# I2CInterface.net
KiCad netlist of a schematic drawn in Altium Designer
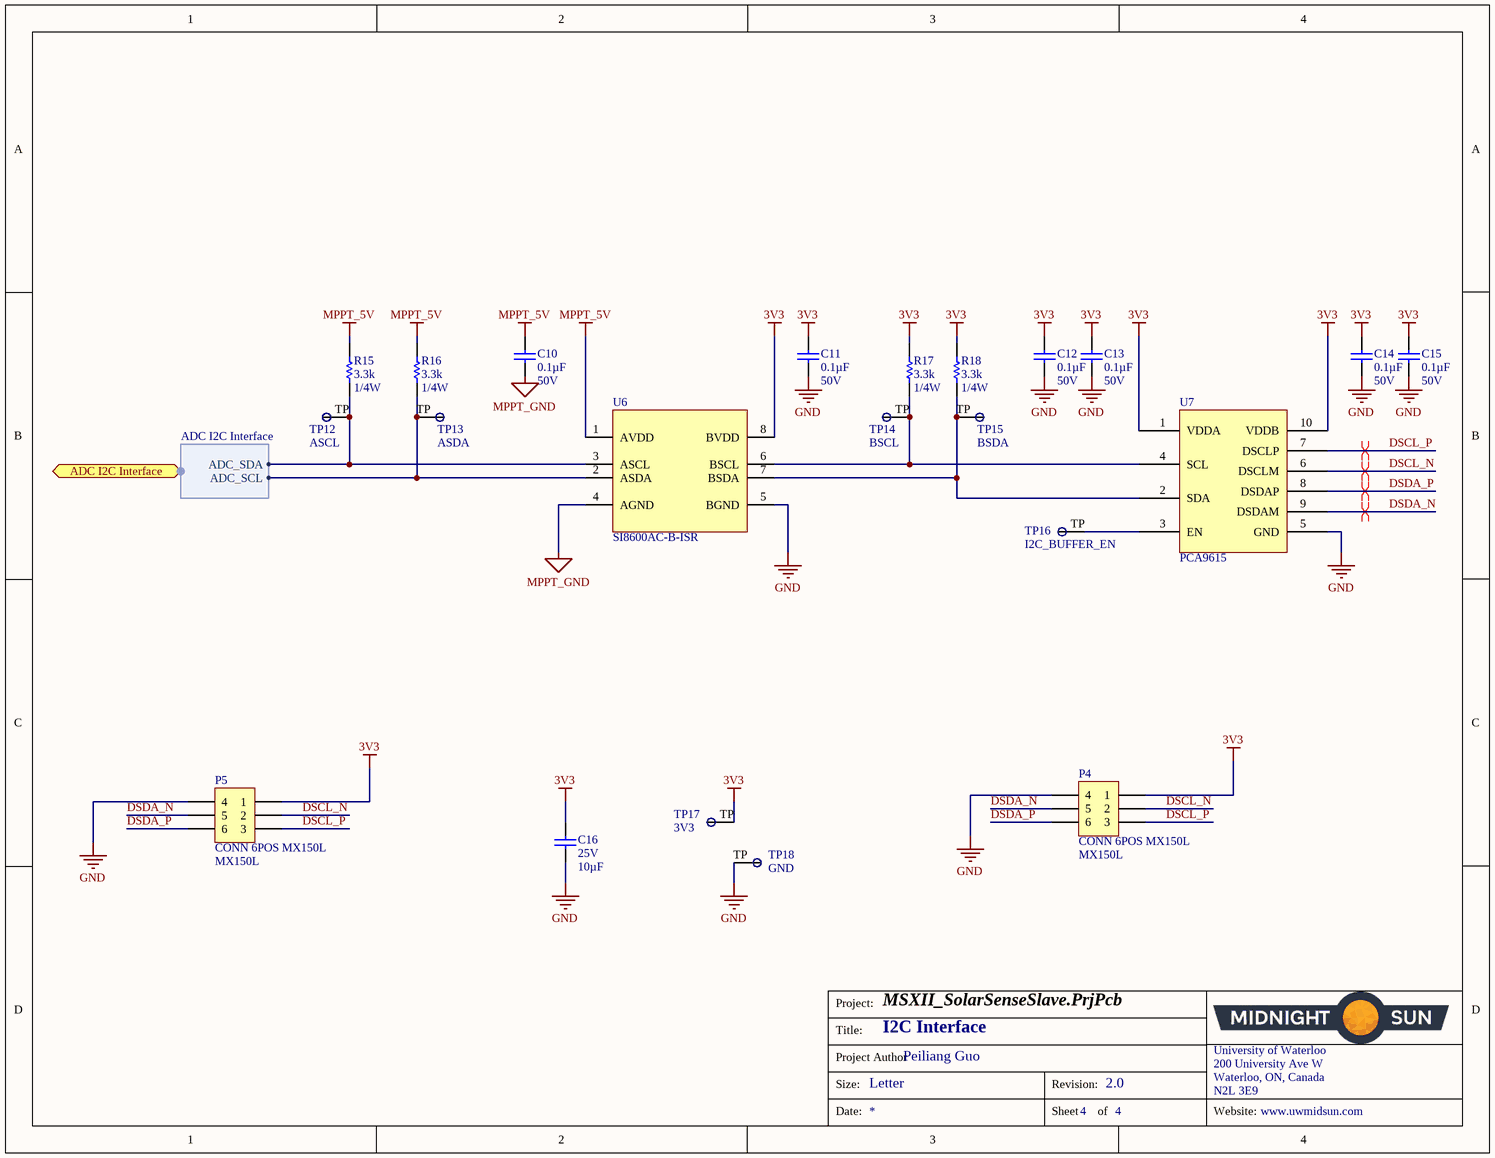
[diagram p0: I2CInterface.SchDoc]

(export (version "E")
  (design (tool "Eeschema 10.0.6"))
  (components
    (comp (ref "C10")
      (value "CAP CER 0.1UF 50V 10% X7R 0603")
      (footprint "CAP, 0603")
      (description "0.10µF ±10% 50V Ceramic Capacitor X7R 0603 (1608 Metric)")
      (fields
        (field (name "TOLERANCE") "±10%")
        (field (name "CAPACITANCE") "0.1µF")
        (field (name "VOLTAGE") "50V")
      )
      (libsource (lib "Schematic Diagrams") (part "CAP CER 0.1UF 50V 10% X7R 0603"))
    )
    (comp (ref "C11")
      (value "CAP CER 0.1UF 50V 10% X7R 0603")
      (footprint "CAP, 0603")
      (description "0.10µF ±10% 50V Ceramic Capacitor X7R 0603 (1608 Metric)")
      (fields
        (field (name "TOLERANCE") "±10%")
        (field (name "CAPACITANCE") "0.1µF")
        (field (name "VOLTAGE") "50V")
      )
      (libsource (lib "Schematic Diagrams") (part "CAP CER 0.1UF 50V 10% X7R 0603"))
    )
    (comp (ref "C12")
      (value "CAP CER 0.1UF 50V 10% X7R 0603")
      (footprint "CAP, 0603")
      (description "0.10µF ±10% 50V Ceramic Capacitor X7R 0603 (1608 Metric)")
      (fields
        (field (name "TOLERANCE") "±10%")
        (field (name "CAPACITANCE") "0.1µF")
        (field (name "VOLTAGE") "50V")
      )
      (libsource (lib "Schematic Diagrams") (part "CAP CER 0.1UF 50V 10% X7R 0603"))
    )
    (comp (ref "C13")
      (value "CAP CER 0.1UF 50V 10% X7R 0603")
      (footprint "CAP, 0603")
      (description "0.10µF ±10% 50V Ceramic Capacitor X7R 0603 (1608 Metric)")
      (fields
        (field (name "TOLERANCE") "±10%")
        (field (name "CAPACITANCE") "0.1µF")
        (field (name "VOLTAGE") "50V")
      )
      (libsource (lib "Schematic Diagrams") (part "CAP CER 0.1UF 50V 10% X7R 0603"))
    )
    (comp (ref "C14")
      (value "CAP CER 0.1UF 50V 10% X7R 0603")
      (footprint "CAP, 0603")
      (description "0.10µF ±10% 50V Ceramic Capacitor X7R 0603 (1608 Metric)")
      (fields
        (field (name "TOLERANCE") "±10%")
        (field (name "CAPACITANCE") "0.1µF")
        (field (name "VOLTAGE") "50V")
      )
      (libsource (lib "Schematic Diagrams") (part "CAP CER 0.1UF 50V 10% X7R 0603"))
    )
    (comp (ref "C15")
      (value "CAP CER 0.1UF 50V 10% X7R 0603")
      (footprint "CAP, 0603")
      (description "0.10µF ±10% 50V Ceramic Capacitor X7R 0603 (1608 Metric)")
      (fields
        (field (name "TOLERANCE") "±10%")
        (field (name "CAPACITANCE") "0.1µF")
        (field (name "VOLTAGE") "50V")
      )
      (libsource (lib "Schematic Diagrams") (part "CAP CER 0.1UF 50V 10% X7R 0603"))
    )
    (comp (ref "C16")
      (value "CAP CER 10uF 25V 10% X5R 0805")
      (footprint "CAP, 0805")
      (description "10µF ±10% 25V Ceramic Capacitor X5R 0805 (2012 Metric)")
      (fields
        (field (name "MANUFACTURER") "Murata Electronics North America")
        (field (name "MANUFACTURER PART NUMBER") "GRM21BR61E106KA73L")
        (field (name "VOLTAGE - RATED") "25V")
        (field (name "CAPACITANCE") "10µF")
      )
      (libsource (lib "Schematic Diagrams") (part "CAP CER 10uF 25V 10% X5R 0805"))
    )
    (comp (ref "P4")
      (value "CONN 6POS MX150L")
      (footprint "CONN, 6POS MX150L")
      (description "Connector Header Panel Mount, Through Hole, Right Angle 6 position 0.230\" (5.84mm)")
      (fields
        (field (name "MANUFACTURER") "Molex")
        (field (name "MANUFACTURER PART NUMBER") "19427-0018")
        (field (name "SERIES") "MX150L")
      )
      (libsource (lib "Schematic Diagrams") (part "CONN 6POS MX150L"))
    )
    (comp (ref "P5")
      (value "CONN 6POS MX150L")
      (footprint "CONN, 6POS MX150L")
      (description "Connector Header Panel Mount, Through Hole, Right Angle 6 position 0.230\" (5.84mm)")
      (fields
        (field (name "MANUFACTURER") "Molex")
        (field (name "MANUFACTURER PART NUMBER") "19427-0018")
        (field (name "SERIES") "MX150L")
      )
      (libsource (lib "Schematic Diagrams") (part "CONN 6POS MX150L"))
    )
    (comp (ref "R15")
      (value "RES 3.3K OHM 1% 1/4W 0603")
      (footprint "RES, 0603")
      (fields
        (field (name "TOLERANCE") "±1%")
        (field (name "RESISTANCE") "3.3k")
        (field (name "POWER") "1/4W")
      )
      (libsource (lib "Schematic Diagrams") (part "RES 3.3K OHM 1% 1/4W 0603"))
    )
    (comp (ref "R16")
      (value "RES 3.3K OHM 1% 1/4W 0603")
      (footprint "RES, 0603")
      (fields
        (field (name "TOLERANCE") "±1%")
        (field (name "RESISTANCE") "3.3k")
        (field (name "POWER") "1/4W")
      )
      (libsource (lib "Schematic Diagrams") (part "RES 3.3K OHM 1% 1/4W 0603"))
    )
    (comp (ref "R17")
      (value "RES 3.3K OHM 1% 1/4W 0603")
      (footprint "RES, 0603")
      (fields
        (field (name "TOLERANCE") "±1%")
        (field (name "RESISTANCE") "3.3k")
        (field (name "POWER") "1/4W")
      )
      (libsource (lib "Schematic Diagrams") (part "RES 3.3K OHM 1% 1/4W 0603"))
    )
    (comp (ref "R18")
      (value "RES 3.3K OHM 1% 1/4W 0603")
      (footprint "RES, 0603")
      (fields
        (field (name "TOLERANCE") "±1%")
        (field (name "RESISTANCE") "3.3k")
        (field (name "POWER") "1/4W")
      )
      (libsource (lib "Schematic Diagrams") (part "RES 3.3K OHM 1% 1/4W 0603"))
    )
    (comp (ref "TP12")
      (value "ASCL")
      (footprint "Test Point")
      (libsource (lib "Schematic Diagrams") (part "Test Point"))
    )
    (comp (ref "TP13")
      (value "ASDA")
      (footprint "Test Point")
      (libsource (lib "Schematic Diagrams") (part "Test Point"))
    )
    (comp (ref "TP14")
      (value "BSCL")
      (footprint "Test Point")
      (libsource (lib "Schematic Diagrams") (part "Test Point"))
    )
    (comp (ref "TP15")
      (value "BSDA")
      (footprint "Test Point")
      (libsource (lib "Schematic Diagrams") (part "Test Point"))
    )
    (comp (ref "TP16")
      (value "I2C_BUFFER_EN")
      (footprint "Test Point")
      (libsource (lib "Schematic Diagrams") (part "Test Point"))
    )
    (comp (ref "TP17")
      (value "3V3")
      (footprint "Test Point")
      (libsource (lib "Schematic Diagrams") (part "Test Point"))
    )
    (comp (ref "TP18")
      (value "GND")
      (footprint "Test Point")
      (libsource (lib "Schematic Diagrams") (part "Test Point"))
    )
    (comp (ref "U6")
      (value "IC DGTL ISO I2C 3.75KV 2CH 8SOIC")
      (footprint "IC DGTL ISO 3.75KV I2C 8SOIC NARROW BODY")
      (description "I²C Digital Isolator 3750Vrms 2 Channel 35kV/µs CMTI 8-SOIC (0.154\", 3.90mm Width)")
      (fields (field (name "MANUFACTURER PART NUMBER 1") "SI8600AC-B-ISR"))
      (libsource (lib "Schematic Diagrams") (part "IC DGTL ISO I2C 3.75KV 2CH 8SOIC"))
    )
    (comp (ref "U7")
      (value "IC DIFFERENTIAL I2C BUFFER PCA9615")
      (footprint "TSSOP50P490X110-10N")
      (description "Buffer, ReDriver 2 Channel 400kHz 10-TSSOP")
      (fields
        (field (name "MANUFACTURER") "NXP USA Inc.")
        (field (name "MANUFACTURER PART NUMBER") "PCA9615DPJ")
        (field (name "BASE PART NUMBER") "PCA9615")
      )
      (libsource (lib "Schematic Diagrams") (part "IC DIFFERENTIAL I2C BUFFER PCA9615"))
    )
  )
  (nets
    (net (code "4") (name "/DSCL_N") (class "Default")
      (node (ref "P4") (pin "2") (pinfunction "2_2") (pintype "passive"))
      (node (ref "P5") (pin "2") (pinfunction "2_2") (pintype "passive"))
      (node (ref "U7") (pin "6") (pinfunction "DSCLM_6") (pintype "passive"))
    )
    (net (code "5") (name "/DSCL_P") (class "Default")
      (node (ref "P4") (pin "3") (pinfunction "3_3") (pintype "passive"))
      (node (ref "P5") (pin "3") (pinfunction "3_3") (pintype "passive"))
      (node (ref "U7") (pin "7") (pinfunction "DSCLP_7") (pintype "passive"))
    )
    (net (code "6") (name "/DSDA_N") (class "Default")
      (node (ref "P4") (pin "5") (pinfunction "5_5") (pintype "passive"))
      (node (ref "P5") (pin "5") (pinfunction "5_5") (pintype "passive"))
      (node (ref "U7") (pin "9") (pinfunction "DSDAM_9") (pintype "passive"))
    )
    (net (code "7") (name "/DSDA_P") (class "Default")
      (node (ref "P4") (pin "6") (pinfunction "6_6") (pintype "passive"))
      (node (ref "P5") (pin "6") (pinfunction "6_6") (pintype "passive"))
      (node (ref "U7") (pin "8") (pinfunction "DSDAP_8") (pintype "passive"))
    )
    (net (code "9") (name "3V3") (class "Default")
      (node (ref "C11") (pin "1") (pinfunction "1_1") (pintype "passive"))
      (node (ref "C12") (pin "1") (pinfunction "1_1") (pintype "passive"))
      (node (ref "C13") (pin "1") (pinfunction "1_1") (pintype "passive"))
      (node (ref "C14") (pin "1") (pinfunction "1_1") (pintype "passive"))
      (node (ref "C15") (pin "1") (pinfunction "1_1") (pintype "passive"))
      (node (ref "C16") (pin "1") (pinfunction "1_1") (pintype "passive"))
      (node (ref "P4") (pin "1") (pinfunction "1_1") (pintype "passive"))
      (node (ref "P5") (pin "1") (pinfunction "1_1") (pintype "passive"))
      (node (ref "R17") (pin "1") (pinfunction "1_1") (pintype "passive"))
      (node (ref "R18") (pin "1") (pinfunction "1_1") (pintype "passive"))
      (node (ref "TP17") (pin "TP") (pinfunction "1_TP") (pintype "passive"))
      (node (ref "U6") (pin "8") (pinfunction "BVDD_8") (pintype "passive"))
      (node (ref "U7") (pin "1") (pinfunction "VDDA_1") (pintype "passive"))
      (node (ref "U7") (pin "10") (pinfunction "VDDB_10") (pintype "passive"))
    )
    (net (code "10") (name "GND") (class "Default")
      (node (ref "C11") (pin "2") (pinfunction "2_2") (pintype "passive"))
      (node (ref "C12") (pin "2") (pinfunction "2_2") (pintype "passive"))
      (node (ref "C13") (pin "2") (pinfunction "2_2") (pintype "passive"))
      (node (ref "C14") (pin "2") (pinfunction "2_2") (pintype "passive"))
      (node (ref "C15") (pin "2") (pinfunction "2_2") (pintype "passive"))
      (node (ref "C16") (pin "2") (pinfunction "2_2") (pintype "passive"))
      (node (ref "P4") (pin "4") (pinfunction "4_4") (pintype "passive"))
      (node (ref "P5") (pin "4") (pinfunction "4_4") (pintype "passive"))
      (node (ref "TP18") (pin "TP") (pinfunction "1_TP") (pintype "passive"))
      (node (ref "U6") (pin "5") (pinfunction "BGND_5") (pintype "passive"))
      (node (ref "U7") (pin "5") (pinfunction "GND_5") (pintype "passive"))
    )
    (net (code "11") (name "MPPT_5V") (class "Default")
      (node (ref "C10") (pin "1") (pinfunction "1_1") (pintype "passive"))
      (node (ref "R15") (pin "1") (pinfunction "1_1") (pintype "passive"))
      (node (ref "R16") (pin "1") (pinfunction "1_1") (pintype "passive"))
      (node (ref "U6") (pin "1") (pinfunction "AVDD_1") (pintype "passive"))
    )
    (net (code "12") (name "MPPT_GND") (class "Default")
      (node (ref "C10") (pin "2") (pinfunction "2_2") (pintype "passive"))
      (node (ref "U6") (pin "4") (pinfunction "AGND_4") (pintype "passive"))
    )
    (net (code "13") (name "Net-(TP12-1)") (class "Default")
      (node (ref "R15") (pin "2") (pinfunction "2_2") (pintype "passive"))
      (node (ref "TP12") (pin "TP") (pinfunction "1_TP") (pintype "passive"))
      (node (ref "U6") (pin "3") (pinfunction "ASCL_3") (pintype "open_collector"))
    )
    (net (code "14") (name "Net-(TP13-1)") (class "Default")
      (node (ref "R16") (pin "2") (pinfunction "2_2") (pintype "passive"))
      (node (ref "TP13") (pin "TP") (pinfunction "1_TP") (pintype "passive"))
      (node (ref "U6") (pin "2") (pinfunction "ASDA_2") (pintype "open_collector"))
    )
    (net (code "15") (name "Net-(TP14-1)") (class "Default")
      (node (ref "R17") (pin "2") (pinfunction "2_2") (pintype "passive"))
      (node (ref "TP14") (pin "TP") (pinfunction "1_TP") (pintype "passive"))
      (node (ref "U6") (pin "6") (pinfunction "BSCL_6") (pintype "passive"))
      (node (ref "U7") (pin "4") (pinfunction "SCL_4") (pintype "passive"))
    )
    (net (code "16") (name "Net-(TP15-1)") (class "Default")
      (node (ref "R18") (pin "2") (pinfunction "2_2") (pintype "passive"))
      (node (ref "TP15") (pin "TP") (pinfunction "1_TP") (pintype "passive"))
      (node (ref "U6") (pin "7") (pinfunction "BSDA_7") (pintype "passive"))
      (node (ref "U7") (pin "2") (pinfunction "SDA_2") (pintype "passive"))
    )
    (net (code "17") (name "Net-(TP16-1)") (class "Default")
      (node (ref "TP16") (pin "TP") (pinfunction "1_TP") (pintype "passive"))
      (node (ref "U7") (pin "3") (pinfunction "EN_3") (pintype "passive"))
    )
  )
)
